# Li_Power_Boost_Converter.net
KiCad netlist of a schematic drawn in EAGLE
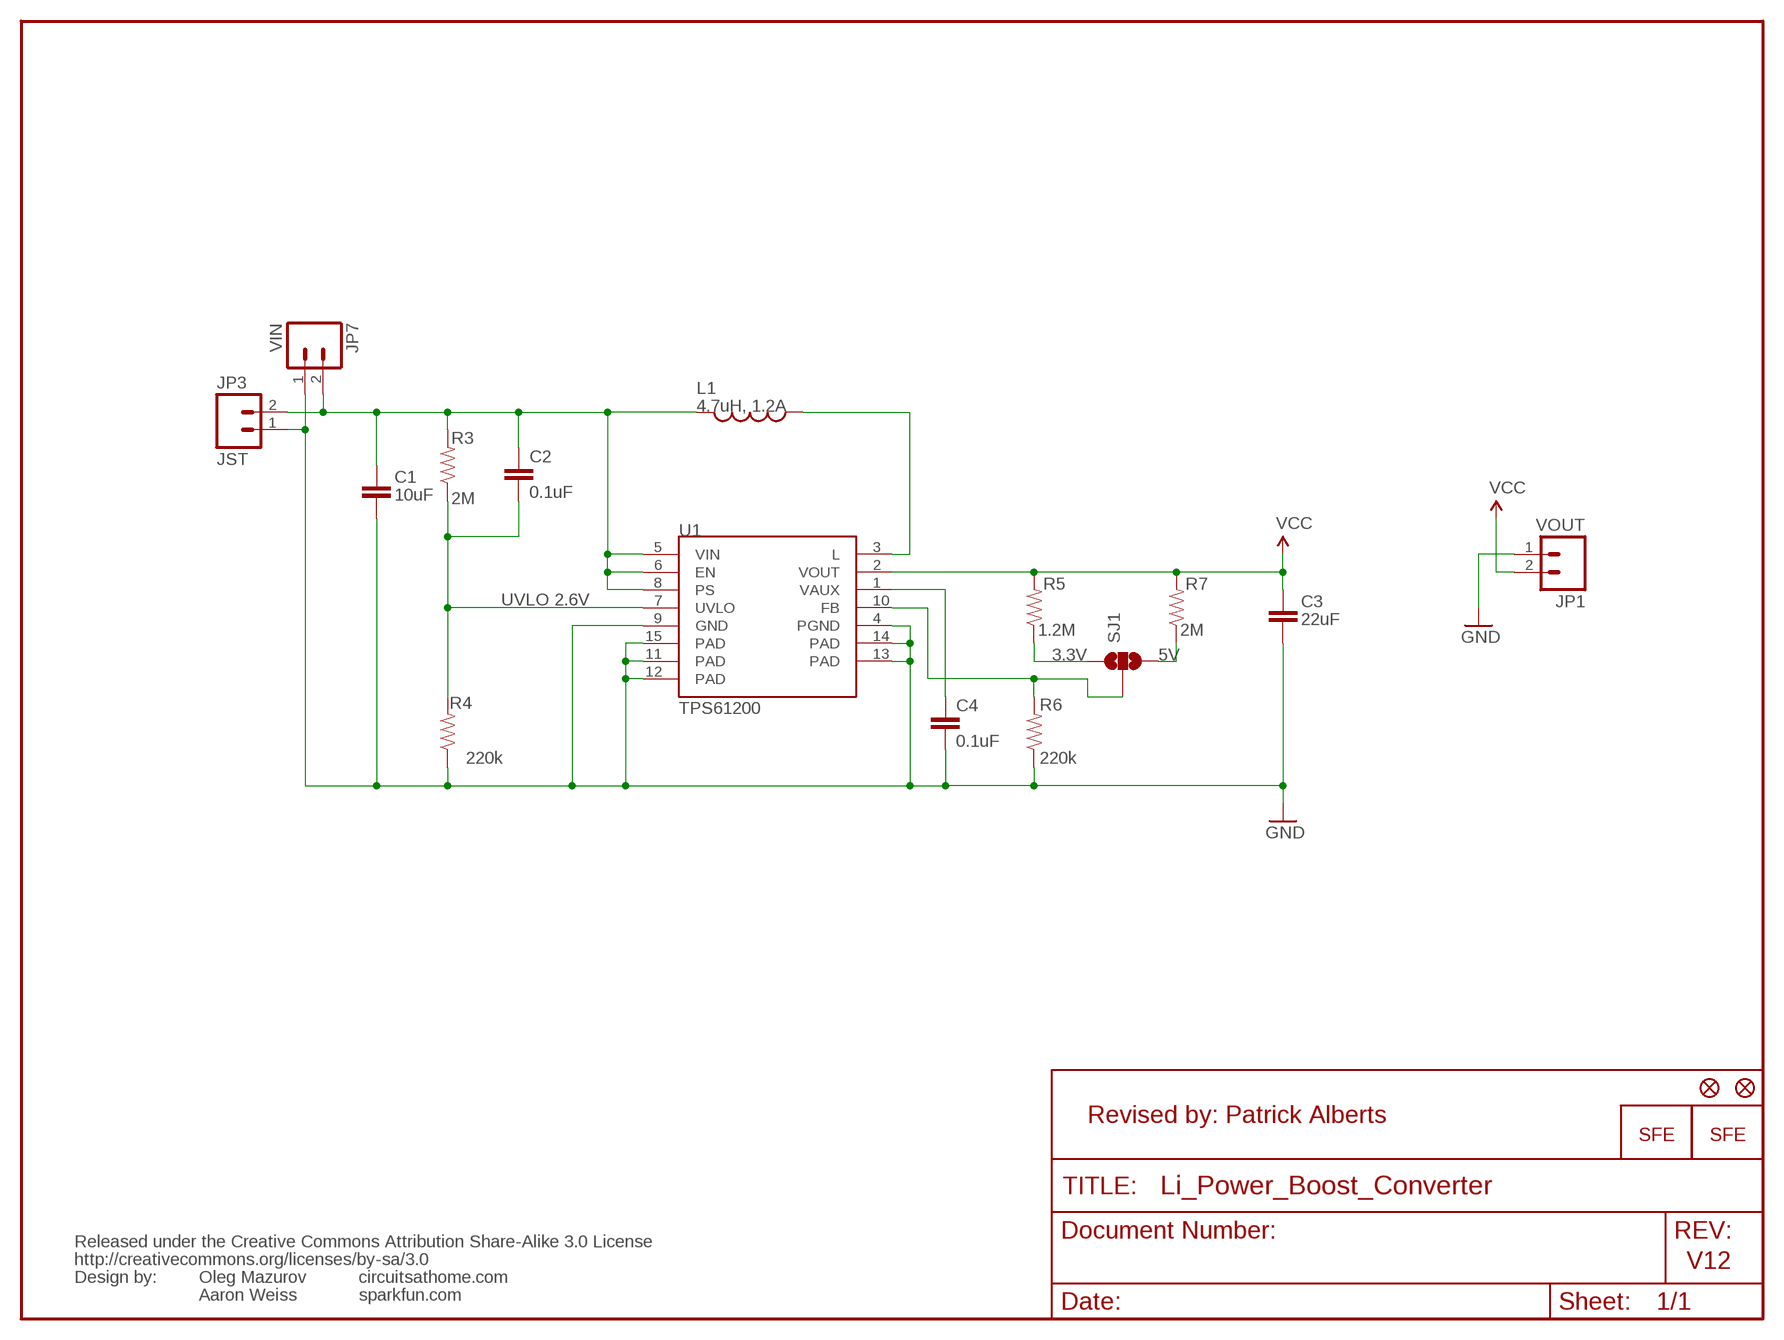
[diagram p0: schematic, sheet 1]

(export (version "E")
  (design (tool "Eeschema 10.0.6"))
  (components
    (comp (ref "C1")
      (value "10uF")
      (footprint "eagle-import:1206")
      (libsource (lib "eagle-import") (part "CAP1206"))
    )
    (comp (ref "C2")
      (value "0.1uF")
      (footprint "eagle-import:0603-CAP")
      (libsource (lib "eagle-import") (part "CAP0603-CAP"))
    )
    (comp (ref "C3")
      (value "22uF")
      (footprint "eagle-import:0805")
      (libsource (lib "eagle-import") (part "CAP0805"))
    )
    (comp (ref "C4")
      (value "0.1uF")
      (footprint "eagle-import:0603-CAP")
      (libsource (lib "eagle-import") (part "CAP0603-CAP"))
    )
    (comp (ref "JP1")
      (value "VOUT")
      (footprint "eagle-import:1X02")
      (libsource (lib "eagle-import") (part "M02PTH"))
    )
    (comp (ref "JP2")
      (value "LOGO-SFESK")
      (footprint "eagle-import:SFE-LOGO-FLAME")
      (libsource (lib "eagle-import") (part "LOGO-SFESK"))
    )
    (comp (ref "JP3")
      (value "JST")
      (footprint "eagle-import:JST-2-SMD")
      (libsource (lib "eagle-import") (part "M02-JST-2MM-SMT"))
    )
    (comp (ref "JP4")
      (value "FIDUCIAL1X2")
      (footprint "eagle-import:FIDUCIAL-1X2")
      (libsource (lib "eagle-import") (part "FIDUCIAL1X2"))
    )
    (comp (ref "JP5")
      (value "FIDUCIAL1X2")
      (footprint "eagle-import:FIDUCIAL-1X2")
      (libsource (lib "eagle-import") (part "FIDUCIAL1X2"))
    )
    (comp (ref "JP6")
      (value "LOGO-SFENEW")
      (footprint "eagle-import:SFE-NEW-WEBLOGO")
      (libsource (lib "eagle-import") (part "LOGO-SFENEW"))
    )
    (comp (ref "JP7")
      (value "VIN")
      (footprint "eagle-import:1X02")
      (libsource (lib "eagle-import") (part "M02PTH"))
    )
    (comp (ref "L1")
      (value "4.7uH, 1.2A")
      (footprint "eagle-import:CDRH2D09")
      (libsource (lib "eagle-import") (part "INDUCTOR."))
    )
    (comp (ref "R3")
      (value "2M")
      (footprint "eagle-import:0603-RES")
      (libsource (lib "eagle-import") (part "RESISTOR0603-RES"))
    )
    (comp (ref "R4")
      (value "220k")
      (footprint "eagle-import:0603-RES")
      (libsource (lib "eagle-import") (part "RESISTOR0603-RES"))
    )
    (comp (ref "R5")
      (value "1.2M")
      (footprint "eagle-import:0603-RES")
      (libsource (lib "eagle-import") (part "RESISTOR0603-RES"))
    )
    (comp (ref "R6")
      (value "220k")
      (footprint "eagle-import:0603-RES")
      (libsource (lib "eagle-import") (part "RESISTOR0603-RES"))
    )
    (comp (ref "R7")
      (value "2M")
      (footprint "eagle-import:0603-RES")
      (libsource (lib "eagle-import") (part "RESISTOR0603-RES"))
    )
    (comp (ref "SJ1")
      (value "SOLDERJUMPER_2WAYPASTE2&3")
      (footprint "eagle-import:SJ_3_PASTE2&3")
      (libsource (lib "eagle-import") (part "SOLDERJUMPER_2WAYPASTE2&3"))
    )
    (comp (ref "U$1")
      (value "CREATIVE_COMMONS")
      (footprint "eagle-import:CREATIVE_COMMONS")
      (libsource (lib "eagle-import") (part "CREATIVE_COMMONS"))
    )
    (comp (ref "U1")
      (value "TPS61200")
      (footprint "eagle-import:QFN-10_PAD")
      (libsource (lib "eagle-import") (part "TPS61200"))
    )
  )
  (nets
    (net (code "1") (name "/3.3V") (class "Default")
      (node (ref "R5") (pin "1") (pinfunction "1_1") (pintype "passive"))
      (node (ref "SJ1") (pin "1") (pinfunction "1_1") (pintype "passive"))
    )
    (net (code "2") (name "/5V") (class "Default")
      (node (ref "R7") (pin "1") (pinfunction "1_1") (pintype "passive"))
      (node (ref "SJ1") (pin "3") (pinfunction "3_3") (pintype "passive"))
    )
    (net (code "3") (name "GND") (class "Default")
      (node (ref "C1") (pin "2") (pinfunction "2_2") (pintype "passive"))
      (node (ref "C3") (pin "2") (pinfunction "2_2") (pintype "passive"))
      (node (ref "C4") (pin "2") (pinfunction "2_2") (pintype "passive"))
      (node (ref "JP1") (pin "1") (pinfunction "1_1") (pintype "passive"))
      (node (ref "JP3") (pin "1") (pinfunction "1_1") (pintype "passive"))
      (node (ref "JP7") (pin "1") (pinfunction "1_1") (pintype "passive"))
      (node (ref "R4") (pin "1") (pinfunction "1_1") (pintype "passive"))
      (node (ref "R6") (pin "1") (pinfunction "1_1") (pintype "passive"))
      (node (ref "U1") (pin "11") (pinfunction "PAD_11") (pintype "power_in"))
      (node (ref "U1") (pin "12") (pinfunction "PAD_12") (pintype "power_in"))
      (node (ref "U1") (pin "13") (pinfunction "PAD_13") (pintype "power_in"))
      (node (ref "U1") (pin "14") (pinfunction "PAD_14") (pintype "power_in"))
      (node (ref "U1") (pin "15") (pinfunction "PAD_15") (pintype "power_in"))
      (node (ref "U1") (pin "4") (pinfunction "PGND_4") (pintype "power_in"))
      (node (ref "U1") (pin "9") (pinfunction "GND_9") (pintype "power_in"))
    )
    (net (code "4") (name "Net-(L1-1)") (class "Default")
      (node (ref "L1") (pin "P$1") (pinfunction "1_P$1") (pintype "passive"))
      (node (ref "U1") (pin "3") (pinfunction "L_3") (pintype "passive"))
    )
    (net (code "5") (name "Net-(L1-2)") (class "Default")
      (node (ref "C1") (pin "1") (pinfunction "1_1") (pintype "passive"))
      (node (ref "C2") (pin "1") (pinfunction "1_1") (pintype "passive"))
      (node (ref "JP3") (pin "2") (pinfunction "2_2") (pintype "passive"))
      (node (ref "JP7") (pin "2") (pinfunction "2_2") (pintype "passive"))
      (node (ref "L1") (pin "P$2") (pinfunction "2_P$2") (pintype "passive"))
      (node (ref "R3") (pin "2") (pinfunction "2_2") (pintype "passive"))
      (node (ref "U1") (pin "5") (pinfunction "VIN_5") (pintype "power_in"))
      (node (ref "U1") (pin "6") (pinfunction "EN_6") (pintype "input"))
      (node (ref "U1") (pin "8") (pinfunction "PS_8") (pintype "input"))
    )
    (net (code "6") (name "Net-(U1-FB)") (class "Default")
      (node (ref "R6") (pin "2") (pinfunction "2_2") (pintype "passive"))
      (node (ref "SJ1") (pin "2") (pinfunction "2_2") (pintype "passive"))
      (node (ref "U1") (pin "10") (pinfunction "FB_10") (pintype "passive"))
    )
    (net (code "7") (name "Net-(U1-UVLO)") (class "Default")
      (node (ref "C2") (pin "2") (pinfunction "2_2") (pintype "passive"))
      (node (ref "R3") (pin "1") (pinfunction "1_1") (pintype "passive"))
      (node (ref "R4") (pin "2") (pinfunction "2_2") (pintype "passive"))
      (node (ref "U1") (pin "7") (pinfunction "UVLO_7") (pintype "passive"))
    )
    (net (code "8") (name "Net-(U1-VAUX)") (class "Default")
      (node (ref "C4") (pin "1") (pinfunction "1_1") (pintype "passive"))
      (node (ref "U1") (pin "1") (pinfunction "VAUX_1") (pintype "passive"))
    )
    (net (code "9") (name "VCC") (class "Default")
      (node (ref "C3") (pin "1") (pinfunction "1_1") (pintype "passive"))
      (node (ref "JP1") (pin "2") (pinfunction "2_2") (pintype "passive"))
      (node (ref "R5") (pin "2") (pinfunction "2_2") (pintype "passive"))
      (node (ref "R7") (pin "2") (pinfunction "2_2") (pintype "passive"))
      (node (ref "U1") (pin "2") (pinfunction "VOUT_2") (pintype "passive"))
    )
  )
)
